# BoardB-LEDs.net
KiCad netlist of a schematic drawn in Altium Designer
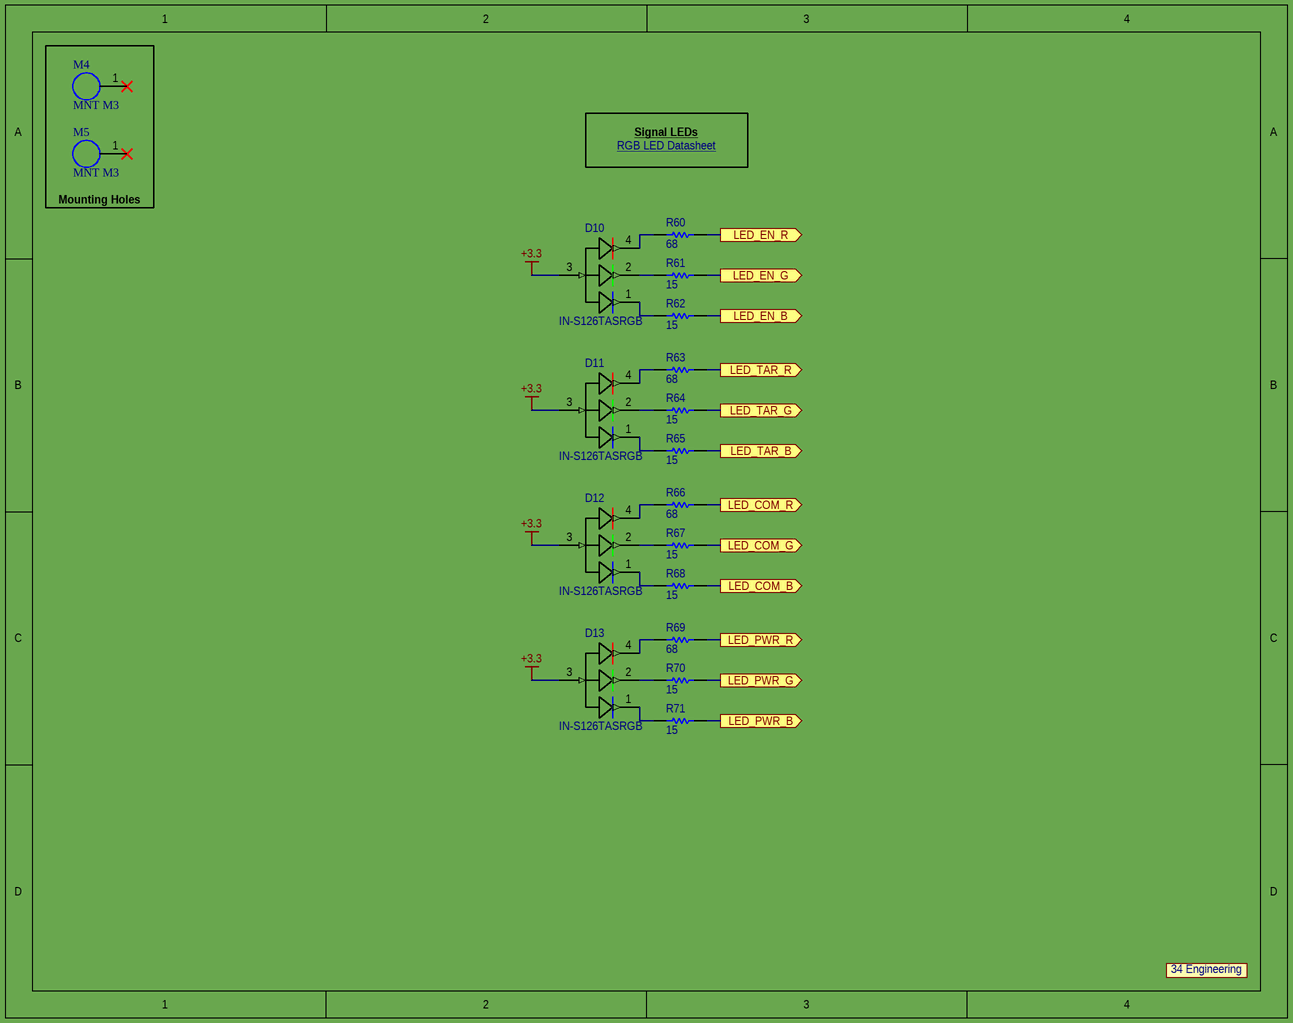
[diagram p0: BoardB-LEDs.SchDoc]

(export (version "E")
  (design (tool "Eeschema 10.0.6"))
  (components
    (comp (ref "D10")
      (value "IN-S126TASRGB")
      (footprint "IN-S126TASRGB")
      (description "LED Tri-Color Blue/Green/Red 470nm/523nm/625nm Automotive 4-Pin Chip 1206(3216Metric) T/R")
      (fields (field (name "MANUFACTURER") "Inolux"))
      (libsource (lib "Virtex") (part "IN-S126TASRGB"))
    )
    (comp (ref "D11")
      (value "IN-S126TASRGB")
      (footprint "IN-S126TASRGB")
      (description "LED Tri-Color Blue/Green/Red 470nm/523nm/625nm Automotive 4-Pin Chip 1206(3216Metric) T/R")
      (fields (field (name "MANUFACTURER") "Inolux"))
      (libsource (lib "Virtex") (part "IN-S126TASRGB"))
    )
    (comp (ref "D12")
      (value "IN-S126TASRGB")
      (footprint "IN-S126TASRGB")
      (description "LED Tri-Color Blue/Green/Red 470nm/523nm/625nm Automotive 4-Pin Chip 1206(3216Metric) T/R")
      (fields (field (name "MANUFACTURER") "Inolux"))
      (libsource (lib "Virtex") (part "IN-S126TASRGB"))
    )
    (comp (ref "D13")
      (value "IN-S126TASRGB")
      (footprint "IN-S126TASRGB")
      (description "LED Tri-Color Blue/Green/Red 470nm/523nm/625nm Automotive 4-Pin Chip 1206(3216Metric) T/R")
      (fields (field (name "MANUFACTURER") "Inolux"))
      (libsource (lib "Virtex") (part "IN-S126TASRGB"))
    )
    (comp (ref "LOGO1")
      (value "34 Engineering Logo")
      (footprint "34EngineeringLogo")
      (description "34 Engineering Silkscreen Logo")
      (libsource (lib "Virtex") (part "34EngineeringLogo"))
    )
    (comp (ref "M4")
      (value "MNT M3")
      (footprint "MNT M3")
      (description "Mounting hole for an M3 bolt")
      (libsource (lib "Virtex") (part "MNT M3"))
    )
    (comp (ref "M5")
      (value "MNT M3")
      (footprint "MNT M3")
      (description "Mounting hole for an M3 bolt")
      (libsource (lib "Virtex") (part "MNT M3"))
    )
    (comp (ref "R60")
      (value "68")
      (footprint "RESC1005X40X25ML05T05")
      (fields (field (name "MANUFACTURER") "Panasonic") (field (name "PART NUMBER") "ERJ2RKF68R0X"))
      (libsource (lib "Altium Content Vault") (part "RES"))
    )
    (comp (ref "R61")
      (value "15")
      (footprint "RESC1005X40X25LL05T05")
      (fields (field (name "MANUFACTURER") "Panasonic") (field (name "PART NUMBER") "ERJ-2RKF15R0X"))
      (libsource (lib "Altium Content Vault") (part "RES"))
    )
    (comp (ref "R62")
      (value "15")
      (footprint "RESC1005X40X25LL05T05")
      (fields (field (name "MANUFACTURER") "Panasonic") (field (name "PART NUMBER") "ERJ-2RKF15R0X"))
      (libsource (lib "Altium Content Vault") (part "RES"))
    )
    (comp (ref "R63")
      (value "68")
      (footprint "RESC1005X40X25ML05T05")
      (fields (field (name "MANUFACTURER") "Panasonic") (field (name "PART NUMBER") "ERJ2RKF68R0X"))
      (libsource (lib "Altium Content Vault") (part "RES"))
    )
    (comp (ref "R64")
      (value "15")
      (footprint "RESC1005X40X25LL05T05")
      (fields (field (name "MANUFACTURER") "Panasonic") (field (name "PART NUMBER") "ERJ-2RKF15R0X"))
      (libsource (lib "Altium Content Vault") (part "RES"))
    )
    (comp (ref "R65")
      (value "15")
      (footprint "RESC1005X40X25LL05T05")
      (fields (field (name "MANUFACTURER") "Panasonic") (field (name "PART NUMBER") "ERJ-2RKF15R0X"))
      (libsource (lib "Altium Content Vault") (part "RES"))
    )
    (comp (ref "R66")
      (value "68")
      (footprint "RESC1005X40X25ML05T05")
      (fields (field (name "MANUFACTURER") "Panasonic") (field (name "PART NUMBER") "ERJ2RKF68R0X"))
      (libsource (lib "Altium Content Vault") (part "RES"))
    )
    (comp (ref "R67")
      (value "15")
      (footprint "RESC1005X40X25LL05T05")
      (fields (field (name "MANUFACTURER") "Panasonic") (field (name "PART NUMBER") "ERJ-2RKF15R0X"))
      (libsource (lib "Altium Content Vault") (part "RES"))
    )
    (comp (ref "R68")
      (value "15")
      (footprint "RESC1005X40X25LL05T05")
      (fields (field (name "MANUFACTURER") "Panasonic") (field (name "PART NUMBER") "ERJ-2RKF15R0X"))
      (libsource (lib "Altium Content Vault") (part "RES"))
    )
    (comp (ref "R69")
      (value "68")
      (footprint "RESC1005X40X25ML05T05")
      (fields (field (name "MANUFACTURER") "Panasonic") (field (name "PART NUMBER") "ERJ2RKF68R0X"))
      (libsource (lib "Altium Content Vault") (part "RES"))
    )
    (comp (ref "R70")
      (value "15")
      (footprint "RESC1005X40X25LL05T05")
      (fields (field (name "MANUFACTURER") "Panasonic") (field (name "PART NUMBER") "ERJ-2RKF15R0X"))
      (libsource (lib "Altium Content Vault") (part "RES"))
    )
    (comp (ref "R71")
      (value "15")
      (footprint "RESC1005X40X25LL05T05")
      (fields (field (name "MANUFACTURER") "Panasonic") (field (name "PART NUMBER") "ERJ-2RKF15R0X"))
      (libsource (lib "Altium Content Vault") (part "RES"))
    )
  )
  (nets
    (net (code "1") (name "+3.3") (class "Default")
      (node (ref "D10") (pin "3") (pintype "input"))
      (node (ref "D11") (pin "3") (pintype "input"))
      (node (ref "D12") (pin "3") (pintype "input"))
      (node (ref "D13") (pin "3") (pintype "input"))
    )
    (net (code "2") (name "/LED_COM_B") (class "Default")
      (node (ref "R68") (pin "2") (pinfunction "2_2") (pintype "passive"))
    )
    (net (code "3") (name "/LED_COM_G") (class "Default")
      (node (ref "R67") (pin "2") (pinfunction "2_2") (pintype "passive"))
    )
    (net (code "4") (name "/LED_COM_R") (class "Default")
      (node (ref "R66") (pin "2") (pinfunction "2_2") (pintype "passive"))
    )
    (net (code "5") (name "/LED_EN_B") (class "Default")
      (node (ref "R62") (pin "2") (pinfunction "2_2") (pintype "passive"))
    )
    (net (code "6") (name "/LED_EN_G") (class "Default")
      (node (ref "R61") (pin "2") (pinfunction "2_2") (pintype "passive"))
    )
    (net (code "7") (name "/LED_EN_R") (class "Default")
      (node (ref "R60") (pin "2") (pinfunction "2_2") (pintype "passive"))
    )
    (net (code "8") (name "/LED_PWR_B") (class "Default")
      (node (ref "R71") (pin "2") (pinfunction "2_2") (pintype "passive"))
    )
    (net (code "9") (name "/LED_PWR_G") (class "Default")
      (node (ref "R70") (pin "2") (pinfunction "2_2") (pintype "passive"))
    )
    (net (code "10") (name "/LED_PWR_R") (class "Default")
      (node (ref "R69") (pin "2") (pinfunction "2_2") (pintype "passive"))
    )
    (net (code "11") (name "/LED_TAR_B") (class "Default")
      (node (ref "R65") (pin "2") (pinfunction "2_2") (pintype "passive"))
    )
    (net (code "12") (name "/LED_TAR_G") (class "Default")
      (node (ref "R64") (pin "2") (pinfunction "2_2") (pintype "passive"))
    )
    (net (code "13") (name "/LED_TAR_R") (class "Default")
      (node (ref "R63") (pin "2") (pinfunction "2_2") (pintype "passive"))
    )
    (net (code "14") (name "Net-(D10-Pad1)") (class "Default")
      (node (ref "D10") (pin "1") (pintype "output"))
      (node (ref "R62") (pin "1") (pinfunction "1_1") (pintype "passive"))
    )
    (net (code "15") (name "Net-(D10-Pad2)") (class "Default")
      (node (ref "D10") (pin "2") (pintype "output"))
      (node (ref "R61") (pin "1") (pinfunction "1_1") (pintype "passive"))
    )
    (net (code "16") (name "Net-(D10-Pad4)") (class "Default")
      (node (ref "D10") (pin "4") (pintype "output"))
      (node (ref "R60") (pin "1") (pinfunction "1_1") (pintype "passive"))
    )
    (net (code "17") (name "Net-(D11-Pad1)") (class "Default")
      (node (ref "D11") (pin "1") (pintype "output"))
      (node (ref "R65") (pin "1") (pinfunction "1_1") (pintype "passive"))
    )
    (net (code "18") (name "Net-(D11-Pad2)") (class "Default")
      (node (ref "D11") (pin "2") (pintype "output"))
      (node (ref "R64") (pin "1") (pinfunction "1_1") (pintype "passive"))
    )
    (net (code "19") (name "Net-(D11-Pad4)") (class "Default")
      (node (ref "D11") (pin "4") (pintype "output"))
      (node (ref "R63") (pin "1") (pinfunction "1_1") (pintype "passive"))
    )
    (net (code "20") (name "Net-(D12-Pad1)") (class "Default")
      (node (ref "D12") (pin "1") (pintype "output"))
      (node (ref "R68") (pin "1") (pinfunction "1_1") (pintype "passive"))
    )
    (net (code "21") (name "Net-(D12-Pad2)") (class "Default")
      (node (ref "D12") (pin "2") (pintype "output"))
      (node (ref "R67") (pin "1") (pinfunction "1_1") (pintype "passive"))
    )
    (net (code "22") (name "Net-(D12-Pad4)") (class "Default")
      (node (ref "D12") (pin "4") (pintype "output"))
      (node (ref "R66") (pin "1") (pinfunction "1_1") (pintype "passive"))
    )
    (net (code "23") (name "Net-(D13-Pad1)") (class "Default")
      (node (ref "D13") (pin "1") (pintype "output"))
      (node (ref "R71") (pin "1") (pinfunction "1_1") (pintype "passive"))
    )
    (net (code "24") (name "Net-(D13-Pad2)") (class "Default")
      (node (ref "D13") (pin "2") (pintype "output"))
      (node (ref "R70") (pin "1") (pinfunction "1_1") (pintype "passive"))
    )
    (net (code "25") (name "Net-(D13-Pad4)") (class "Default")
      (node (ref "D13") (pin "4") (pintype "output"))
      (node (ref "R69") (pin "1") (pinfunction "1_1") (pintype "passive"))
    )
    (net (code "26") (name "unconnected-(M4-Pad1)") (class "Default")
      (node (ref "M4") (pin "1") (pintype "passive+no_connect"))
    )
    (net (code "27") (name "unconnected-(M5-Pad1)") (class "Default")
      (node (ref "M5") (pin "1") (pintype "passive+no_connect"))
    )
  )
)
